# 13_LED_BACKLIGHT.net
KiCad netlist of a schematic drawn in Altium Designer
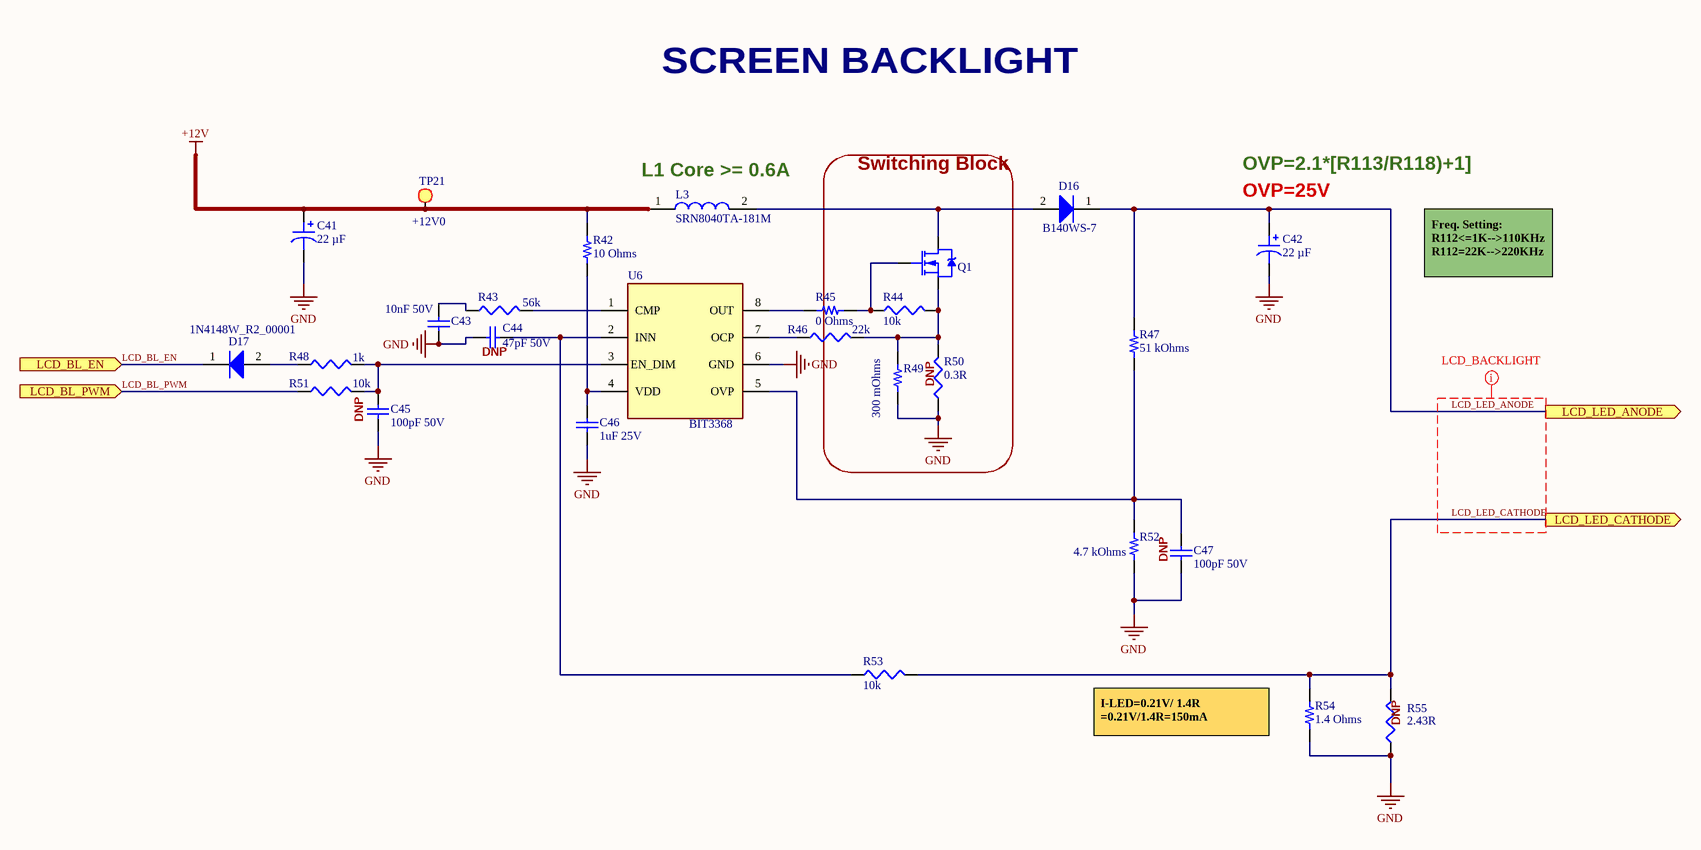
[diagram p0: 13_LED_BACKLIGHT.SchDoc]

(export (version "E")
  (design (tool "Eeschema 10.0.6"))
  (components
    (comp (ref "C41")
      (value "22 µF")
      (footprint "CAP ALSMD 6.6MM H5.4MM")
      (description "CAP ALUM 22UF 20% 50V SMD")
      (fields (field (name "PART NUMBER") "865080643008") (field (name "MANUFACTURER") "Würth Elektronik"))
      (libsource (lib "Celestial Altium Library - altium_library") (part "Polarised Capacitor"))
    )
    (comp (ref "C42")
      (value "22 µF")
      (footprint "CAP ALSMD 6.6MM H5.4MM")
      (description "CAP ALUM 22UF 20% 50V SMD")
      (fields (field (name "PART NUMBER") "865080643008") (field (name "MANUFACTURER") "Würth Elektronik"))
      (libsource (lib "Celestial Altium Library - altium_library") (part "Polarised Capacitor"))
    )
    (comp (ref "C43")
      (value "10nF 50V")
      (footprint "SMC0603")
      (description "10000 pF ±10% 50V Ceramic Capacitor X7R 0603 (1608 Metric)")
      (fields
        (field (name "MANUFACTURER PART NUMBER") "CL10B103KB8NNNC")
        (field (name "LCSC PART NUMBER") "C1589")
      )
      (libsource (lib "HW_HOLLAND_NCDM_MONITOR_R1") (part "CAP0603_10NF_50V"))
    )
    (comp (ref "C44")
      (value "47pF 50V")
      (footprint "SMC0603")
      (description "47 pF ±5% 50V Ceramic Capacitor C0G, NP0 0603 (1608 Metric)")
      (fields
        (field (name "MANUFACTURER PART NUMBER") "CC0603JRNPO9BN470")
        (field (name "LCSC PART NUMBER") "C105622")
      )
      (libsource (lib "HW_HOLLAND_NCDM_MONITOR_R1") (part "CAP0603_47PF_50V"))
    )
    (comp (ref "C45")
      (value "100pF 50V")
      (footprint "SMC0603")
      (description "100 pF ±5% 50V Ceramic Capacitor C0G, NP0 0603 (1608 Metric)")
      (fields
        (field (name "MANUFACTURER PART NUMBER") "06035A101JAT2A")
        (field (name "LCSC PART NUMBER") "C14665")
      )
      (libsource (lib "HW_HOLLAND_NCDM_MONITOR_R1") (part "CAP0603_100PF_50V"))
    )
    (comp (ref "C46")
      (value "1uF 25V")
      (footprint "SMC0603")
      (description "1 µF ±10% 25V Ceramic Capacitor X5R 0603 (1608 Metric)")
      (fields
        (field (name "MANUFACTURER PART NUMBER") "CL10A105KA8NNNC")
        (field (name "LCSC PART NUMBER") "C5673")
      )
      (libsource (lib "HW_HOLLAND_NCDM_MONITOR_R1") (part "CAP0603_1UF_50V"))
    )
    (comp (ref "C47")
      (value "100pF 50V")
      (footprint "SMC0603")
      (description "100 pF ±5% 50V Ceramic Capacitor C0G, NP0 0603 (1608 Metric)")
      (fields
        (field (name "MANUFACTURER PART NUMBER") "06035A101JAT2A")
        (field (name "LCSC PART NUMBER") "C14665")
      )
      (libsource (lib "HW_HOLLAND_NCDM_MONITOR_R1") (part "CAP0603_100PF_50V"))
    )
    (comp (ref "D16")
      (value "DIODE SCHOTTKY 40V 1A SOD323")
      (footprint "SOD-323_L1.8-W1.3-LS2.5-RD")
      (description "Diode 40 V 1A Surface Mount SOD-323")
      (fields
        (field (name "LCSC MANUFACTURER PART NUMBER") "B140WS-7")
        (field (name "LCSC PART NUMBER") "C95171")
        (field (name "MANUFACTURER PART NUMBER") "B140WS-7")
      )
      (libsource (lib "HW_HOLLAND_NCDM_MONITOR_R1") (part "BS140WS-7"))
    )
    (comp (ref "D17")
      (value "Diode 75 V 200mA Surface Mount SOD-123")
      (footprint "SOD-123_L2.8-W1.8-LS3.7-RD")
      (fields (field (name "MANUFACTURER PART NUMBER") "1N4148W_R2_00001"))
      (libsource (lib "HW_HOLLAND_NCDM_MONITOR_R1") (part "1N4148W_R2_00001"))
    )
    (comp (ref "L3")
      (value "SRN8040TA-181M")
      (footprint "SamacSys:INDPM8080X450N")
      (description "FIXED IND 180UH 910MA 490MOHM SM")
      (fields (field (name "MOUSER PART NUMBER") "652-SRN8040TA-181M"))
      (libsource (lib "HW_HOLLAND_NCDM_MONITOR_R1") (part "SRN8040TA-181M"))
    )
    (comp (ref "Q1")
      (value "MOSFET N-CH 100V 30A TO252-3")
      (footprint "TO-252_L6.5-W6.1-P4.58-LS9.9-BR")
      (description "N-Channel 100 V 30A (Tc) 57W (Tc) Surface Mount PG-TO252-3-11")
      (fields (field (name "MANUFACTURER PART NUMBER") "IPD30N10S3L34ATMA1"))
      (libsource (lib "HW_HOLLAND_NCDM_MONITOR_R1") (part "IPD30N10S3L34ATMA1"))
    )
    (comp (ref "R42")
      (value "10 Ohms")
      (footprint "RES 0805_2012")
      (description "RES SMD 10 OHM 1% 1/5W 0805")
      (fields
        (field (name "PART NUMBER") "MCU08050C1009FP500")
        (field (name "MANUFACTURER") "Vishay Beyschlag")
      )
      (libsource (lib "Celestial Altium Library - altium_library") (part "Resistor"))
    )
    (comp (ref "R43")
      (value "56k")
      (footprint "SMR0603")
      (description "56 kOhms ±1% 0.1W, 1/10W Chip Resistor 0603 (1608 Metric) Moisture Resistant Thick Film")
      (fields
        (field (name "MANUFACTURER PART NUMBER") "RC0603FR-0756KL")
        (field (name "LCSC PART NUMBER") "C114630")
      )
      (libsource (lib "HW_HOLLAND_NCDM_MONITOR_R1") (part "RES0603_56K_%1"))
    )
    (comp (ref "R44")
      (value "10k")
      (footprint "SMR0603")
      (description "10 kOhms ±1% 0.1W, 1/10W Chip Resistor 0603 (1608 Metric) Moisture Resistant Thick Film")
      (fields
        (field (name "MANUFACTURER PART NUMBER") "RC0603FR-0710KL")
        (field (name "LCSC PART NUMBER") "C98220")
      )
      (libsource (lib "HW_HOLLAND_NCDM_MONITOR_R1") (part "RES0603_10K_%1"))
    )
    (comp (ref "R45")
      (value "0 Ohms")
      (footprint "RES 0603_1608")
      (description "RES 0 OHM JUMPER 1/10W 0603")
      (fields (field (name "PART NUMBER") "RC0603JR-070RL") (field (name "MANUFACTURER") "Yageo"))
      (libsource (lib "Celestial Altium Library - altium_library") (part "Resistor"))
    )
    (comp (ref "R46")
      (value "22k")
      (footprint "SMR0603")
      (description "22K")
      (fields
        (field (name "MANUFACTURER PART NUMBER") "RC0603FR-0722KL")
        (field (name "LCSC PART NUMBER") "C114065")
      )
      (libsource (lib "HW_HOLLAND_NCDM_MONITOR_R1") (part "RES0603_22K_%1"))
    )
    (comp (ref "R47")
      (value "51 kOhms")
      (footprint "RES 0603_1608")
      (description "RES SMD 51K OHM 1% 1/10W 0603")
      (fields (field (name "PART NUMBER") "CRCW060351K0FKEA") (field (name "MANUFACTURER") "Vishay Dale"))
      (libsource (lib "Celestial Altium Library - altium_library") (part "Resistor"))
    )
    (comp (ref "R48")
      (value "1k")
      (footprint "SMR0603")
      (description "1 kOhms ±1% 0.1W, 1/10W Chip Resistor 0603 (1608 Metric) Moisture Resistant Thick Film")
      (fields
        (field (name "MANUFACTURER PART NUMBER") "RC0603FR-071KL")
        (field (name "LCSC PART NUMBER") "C22548")
      )
      (libsource (lib "HW_HOLLAND_NCDM_MONITOR_R1") (part "RES0603_1K_%1"))
    )
    (comp (ref "R49")
      (value "300 mOhms")
      (footprint "RES 0805_2012")
      (description "RES 0.3 OHM 1% 1/4W 0805")
      (fields
        (field (name "PART NUMBER") "CSR0805FKR300")
        (field (name "MANUFACTURER") "Stackpole Electronics Inc")
      )
      (libsource (lib "Celestial Altium Library - altium_library") (part "Resistor"))
    )
    (comp (ref "R50")
      (value "0.3R")
      (footprint "SMR0805")
      (description "125mW Thick Film Resistors ±1% 300mΩ 0805 Chip Resistor - Surface Mount ROHS")
      (fields
        (field (name "MANUFACTURER PART NUMBER") "0805W8F300LT5E")
        (field (name "LCSC PART NUMBER") "C247157")
      )
      (libsource (lib "HW_HOLLAND_NCDM_MONITOR_R1") (part "RES0805_0.3R_%1"))
    )
    (comp (ref "R51")
      (value "10k")
      (footprint "SMR0603")
      (description "10 kOhms ±1% 0.1W, 1/10W Chip Resistor 0603 (1608 Metric) Moisture Resistant Thick Film")
      (fields
        (field (name "MANUFACTURER PART NUMBER") "RC0603FR-0710KL")
        (field (name "LCSC PART NUMBER") "C98220")
      )
      (libsource (lib "HW_HOLLAND_NCDM_MONITOR_R1") (part "RES0603_10K_%1"))
    )
    (comp (ref "R52")
      (value "4.7 kOhms")
      (footprint "RES 0603_1608")
      (description "RES SMD 4.7K OHM 0.1% 1/10W 0603")
      (fields
        (field (name "PART NUMBER") "ERA-3AEB472V")
        (field (name "MANUFACTURER") "Panasonic Electronic Components")
      )
      (libsource (lib "Celestial Altium Library - altium_library") (part "Resistor"))
    )
    (comp (ref "R53")
      (value "10k")
      (footprint "SMR0603")
      (description "10 kOhms ±1% 0.1W, 1/10W Chip Resistor 0603 (1608 Metric) Moisture Resistant Thick Film")
      (fields
        (field (name "MANUFACTURER PART NUMBER") "RC0603FR-0710KL")
        (field (name "LCSC PART NUMBER") "C98220")
      )
      (libsource (lib "HW_HOLLAND_NCDM_MONITOR_R1") (part "RES0603_10K_%1"))
    )
    (comp (ref "R54")
      (value "1.4 Ohms")
      (footprint "RES 0805_2012")
      (description "RES 1.4 OHM 1% 1/4W 0805")
      (fields
        (field (name "PART NUMBER") "RK73H2ATTD1R40F")
        (field (name "MANUFACTURER") "KOA Speer Electronics, Inc.")
      )
      (libsource (lib "Celestial Altium Library - altium_library") (part "Resistor"))
    )
    (comp (ref "R55")
      (value "2.43R")
      (footprint "SMR0805")
      (description "125mW Thick Film Resistors ±1% 2.43Ω 0805 Chip Resistor - Surface Mount ROHS")
      (fields
        (field (name "MANUFACTURER PART NUMBER") "FRC0805F2R43TS")
        (field (name "LCSC PART NUMBER") "C2933405")
      )
      (libsource (lib "HW_HOLLAND_NCDM_MONITOR_R1") (part "RES0805_2R43_%1"))
    )
    (comp (ref "TP21")
      (value "+12V0")
      (footprint "TEST_POINT")
      (libsource (lib "HW_HOLLAND_NCDM_MONITOR_R1") (part "TP_1"))
    )
    (comp (ref "U6")
      (value "BIT3368 LED DRIVER CONTROLLER")
      (footprint "SOP-8_L4.9-W3.9-P1.27-LS6.0-BL")
      (description "High Performance PWM Controller")
      (fields
        (field (name "MANUFACTURER") "BITEK")
        (field (name "LSCS PART NUMBER") "C5252694")
        (field (name "MANUFACTURER PART NUMBER") "BIT3368")
      )
      (libsource (lib "HW_HOLLAND_NCDM_MONITOR_R1") (part "BIT3368"))
    )
  )
  (nets
    (net (code "1") (name "+12V") (class "Default")
      (node (ref "C41") (pin "1") (pinfunction "1_1") (pintype "passive"))
      (node (ref "L3") (pin "1") (pinfunction "1_1") (pintype "passive"))
      (node (ref "R42") (pin "2") (pinfunction "2_2") (pintype "passive"))
      (node (ref "TP21") (pin "1") (pinfunction "TP_1") (pintype "passive"))
    )
    (net (code "2") (name "/LCD_BL_EN") (class "Default")
      (node (ref "D17") (pin "1") (pinfunction "K_1") (pintype "passive"))
    )
    (net (code "3") (name "/LCD_BL_PWM") (class "Default")
      (node (ref "R51") (pin "1") (pinfunction "1_1") (pintype "passive"))
    )
    (net (code "4") (name "/LCD_LED_ANODE") (class "Default")
      (node (ref "C42") (pin "1") (pinfunction "1_1") (pintype "passive"))
      (node (ref "D16") (pin "1") (pinfunction "K_1") (pintype "passive"))
      (node (ref "R47") (pin "2") (pinfunction "2_2") (pintype "passive"))
    )
    (net (code "5") (name "/LCD_LED_CATHODE") (class "Default")
      (node (ref "R53") (pin "2") (pinfunction "2_2") (pintype "passive"))
      (node (ref "R54") (pin "2") (pinfunction "2_2") (pintype "passive"))
      (node (ref "R55") (pin "2") (pinfunction "2_2") (pintype "passive"))
    )
    (net (code "6") (name "GND") (class "Default")
      (node (ref "C41") (pin "2") (pinfunction "2_2") (pintype "passive"))
      (node (ref "C42") (pin "2") (pinfunction "2_2") (pintype "passive"))
      (node (ref "C43") (pin "1") (pinfunction "1_1") (pintype "passive"))
      (node (ref "C44") (pin "1") (pinfunction "1_1") (pintype "passive"))
      (node (ref "C45") (pin "1") (pinfunction "1_1") (pintype "passive"))
      (node (ref "C46") (pin "1") (pinfunction "1_1") (pintype "passive"))
      (node (ref "C47") (pin "1") (pinfunction "1_1") (pintype "passive"))
      (node (ref "R49") (pin "1") (pinfunction "1_1") (pintype "passive"))
      (node (ref "R50") (pin "1") (pinfunction "1_1") (pintype "passive"))
      (node (ref "R52") (pin "1") (pinfunction "1_1") (pintype "passive"))
      (node (ref "R54") (pin "1") (pinfunction "1_1") (pintype "passive"))
      (node (ref "R55") (pin "1") (pinfunction "1_1") (pintype "passive"))
      (node (ref "U6") (pin "6") (pinfunction "GND_6") (pintype "passive"))
    )
    (net (code "7") (name "Net-(C43-Pad2)") (class "Default")
      (node (ref "C43") (pin "2") (pinfunction "2_2") (pintype "passive"))
      (node (ref "R43") (pin "1") (pinfunction "1_1") (pintype "passive"))
    )
    (net (code "8") (name "Net-(D16-A)") (class "Default")
      (node (ref "D16") (pin "2") (pinfunction "A_2") (pintype "passive"))
      (node (ref "L3") (pin "2") (pinfunction "2_2") (pintype "passive"))
      (node (ref "Q1") (pin "2") (pinfunction "D_2") (pintype "passive"))
    )
    (net (code "9") (name "Net-(D17-A)") (class "Default")
      (node (ref "D17") (pin "2") (pinfunction "A_2") (pintype "passive"))
      (node (ref "R48") (pin "1") (pinfunction "1_1") (pintype "passive"))
    )
    (net (code "10") (name "Net-(Q1-G)") (class "Default")
      (node (ref "Q1") (pin "1") (pinfunction "G_1") (pintype "passive"))
      (node (ref "R44") (pin "1") (pinfunction "1_1") (pintype "passive"))
      (node (ref "R45") (pin "2") (pinfunction "2_2") (pintype "passive"))
    )
    (net (code "11") (name "Net-(Q1-S)") (class "Default")
      (node (ref "Q1") (pin "3") (pinfunction "S_3") (pintype "passive"))
      (node (ref "R44") (pin "2") (pinfunction "2_2") (pintype "passive"))
      (node (ref "R46") (pin "2") (pinfunction "2_2") (pintype "passive"))
      (node (ref "R49") (pin "2") (pinfunction "2_2") (pintype "passive"))
      (node (ref "R50") (pin "2") (pinfunction "2_2") (pintype "passive"))
    )
    (net (code "12") (name "Net-(U6-CMP)") (class "Default")
      (node (ref "R43") (pin "2") (pinfunction "2_2") (pintype "passive"))
      (node (ref "U6") (pin "1") (pinfunction "CMP_1") (pintype "passive"))
    )
    (net (code "13") (name "Net-(U6-EN_DIM)") (class "Default")
      (node (ref "C45") (pin "2") (pinfunction "2_2") (pintype "passive"))
      (node (ref "R48") (pin "2") (pinfunction "2_2") (pintype "passive"))
      (node (ref "R51") (pin "2") (pinfunction "2_2") (pintype "passive"))
      (node (ref "U6") (pin "3") (pinfunction "EN_DIM_3") (pintype "passive"))
    )
    (net (code "14") (name "Net-(U6-INN)") (class "Default")
      (node (ref "C44") (pin "2") (pinfunction "2_2") (pintype "passive"))
      (node (ref "R53") (pin "1") (pinfunction "1_1") (pintype "passive"))
      (node (ref "U6") (pin "2") (pinfunction "INN_2") (pintype "passive"))
    )
    (net (code "15") (name "Net-(U6-OCP)") (class "Default")
      (node (ref "R46") (pin "1") (pinfunction "1_1") (pintype "passive"))
      (node (ref "U6") (pin "7") (pinfunction "OCP_7") (pintype "passive"))
    )
    (net (code "16") (name "Net-(U6-OUT)") (class "Default")
      (node (ref "R45") (pin "1") (pinfunction "1_1") (pintype "passive"))
      (node (ref "U6") (pin "8") (pinfunction "OUT_8") (pintype "passive"))
    )
    (net (code "17") (name "Net-(U6-OVP)") (class "Default")
      (node (ref "C47") (pin "2") (pinfunction "2_2") (pintype "passive"))
      (node (ref "R47") (pin "1") (pinfunction "1_1") (pintype "passive"))
      (node (ref "R52") (pin "2") (pinfunction "2_2") (pintype "passive"))
      (node (ref "U6") (pin "5") (pinfunction "OVP_5") (pintype "passive"))
    )
    (net (code "18") (name "Net-(U6-VDD)") (class "Default")
      (node (ref "C46") (pin "2") (pinfunction "2_2") (pintype "passive"))
      (node (ref "R42") (pin "1") (pinfunction "1_1") (pintype "passive"))
      (node (ref "U6") (pin "4") (pinfunction "VDD_4") (pintype "passive"))
    )
  )
)
